# Main_Board_V1_0.net
KiCad netlist of a schematic drawn in EAGLE
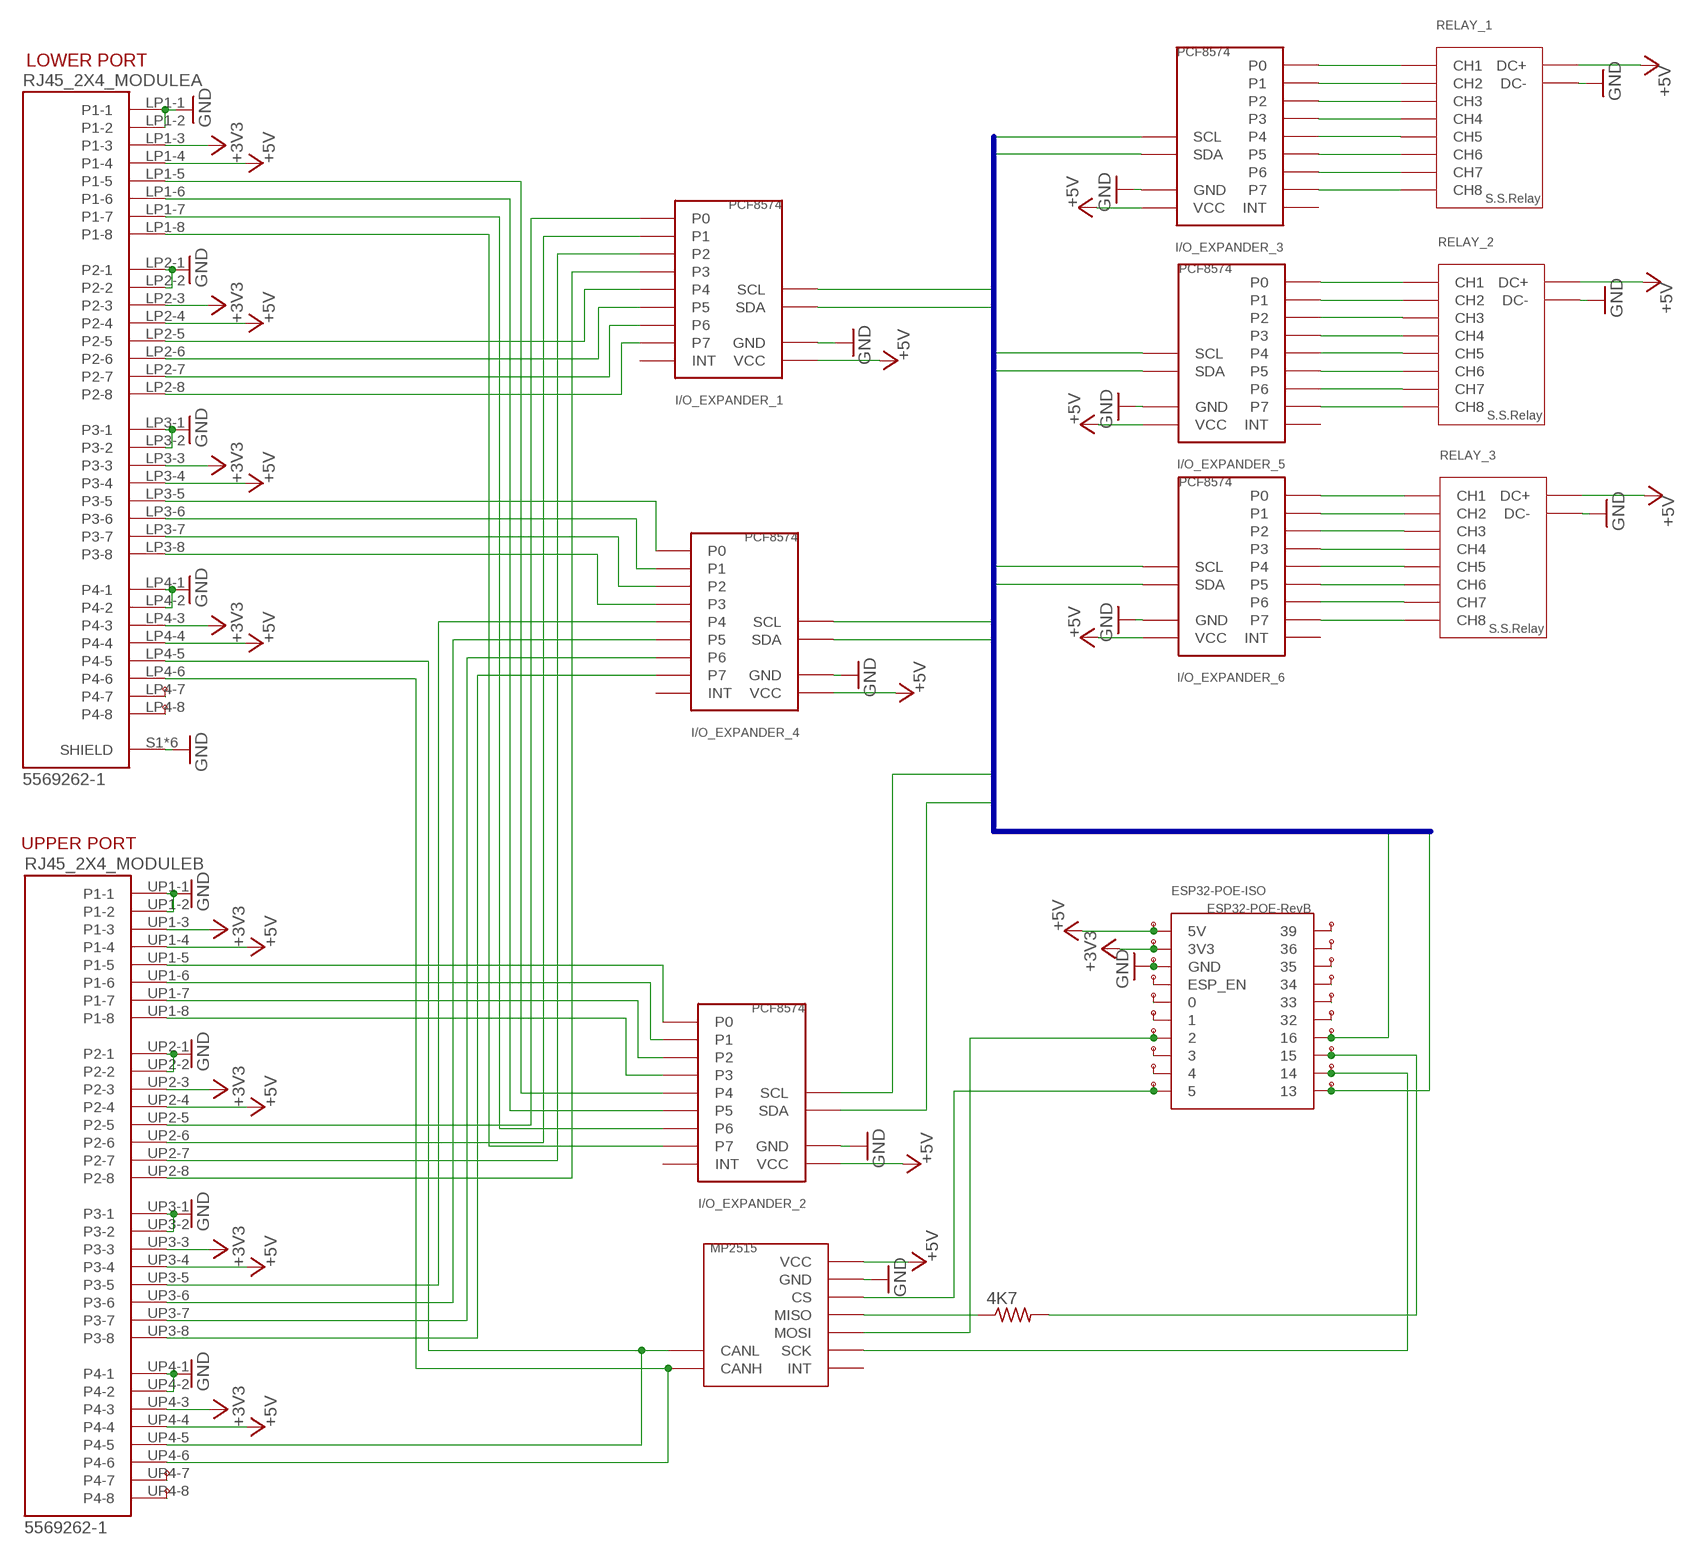
[diagram p0: schematic, sheet 1]

(export (version "E")
  (design (tool "Eeschema 10.0.6"))
  (components
    (comp (ref "4K7")
      (value "R-US_0207/10")
      (footprint "eagle-import:0207_10")
      (libsource (lib "eagle-import") (part "R-US_0207/10"))
    )
    (comp (ref "ESP32-POE-ISO")
      (value "ESP-POE")
      (footprint "eagle-import:ESP-POE")
      (libsource (lib "eagle-import") (part "ESP-POE"))
    )
    (comp (ref "I/O_EXPANDER_1")
      (value "PCF8574-MODULE_ESPELHADO")
      (footprint "eagle-import:PCF8574-MODULE_ESPELHADO")
      (libsource (lib "eagle-import") (part "PCF8574-MODULE_ESPELHADO"))
    )
    (comp (ref "I/O_EXPANDER_2")
      (value "PCF8574-MODULE_ESPELHADO")
      (footprint "eagle-import:PCF8574-MODULE_ESPELHADO")
      (libsource (lib "eagle-import") (part "PCF8574-MODULE_ESPELHADO"))
    )
    (comp (ref "I/O_EXPANDER_3")
      (value "PCF8574-MODULE_ESPELHADO")
      (footprint "eagle-import:PCF8574-MODULE_ESPELHADO")
      (libsource (lib "eagle-import") (part "PCF8574-MODULE_ESPELHADO"))
    )
    (comp (ref "I/O_EXPANDER_4")
      (value "PCF8574-MODULE_ESPELHADO")
      (footprint "eagle-import:PCF8574-MODULE_ESPELHADO")
      (libsource (lib "eagle-import") (part "PCF8574-MODULE_ESPELHADO"))
    )
    (comp (ref "I/O_EXPANDER_5")
      (value "PCF8574-MODULE_ESPELHADO")
      (footprint "eagle-import:PCF8574-MODULE_ESPELHADO")
      (libsource (lib "eagle-import") (part "PCF8574-MODULE_ESPELHADO"))
    )
    (comp (ref "I/O_EXPANDER_6")
      (value "PCF8574-MODULE_ESPELHADO")
      (footprint "eagle-import:PCF8574-MODULE_ESPELHADO")
      (libsource (lib "eagle-import") (part "PCF8574-MODULE_ESPELHADO"))
    )
    (comp (ref "RELAY_1")
      (value "SSR_M_FULL_SEM_LIGACOES")
      (footprint "eagle-import:SSR_M_SEM_LIGACOES")
      (libsource (lib "eagle-import") (part "SSR_M_FULL_SEM_LIGACOES"))
    )
    (comp (ref "RELAY_2")
      (value "SSR_M_FULL_SEM_LIGACOES")
      (footprint "eagle-import:SSR_M_SEM_LIGACOES")
      (libsource (lib "eagle-import") (part "SSR_M_FULL_SEM_LIGACOES"))
    )
    (comp (ref "RELAY_3")
      (value "SSR_M_FULL_SEM_LIGACOES")
      (footprint "eagle-import:SSR_M_SEM_LIGACOES")
      (libsource (lib "eagle-import") (part "SSR_M_FULL_SEM_LIGACOES"))
    )
    (comp (ref "RJ45_2X4_MODULE")
      (value "5569262-1")
      (footprint "eagle-import:TE_5569262-1")
      (fields (field (name "MF") "TE Connectivity"))
      (libsource (lib "eagle-import") (part "5569262-1"))
    )
    (comp (ref "U$1") (value "TP") (footprint "eagle-import:TP") (libsource (lib "eagle-import") (part "TP")))
    (comp (ref "U$2") (value "TP") (footprint "eagle-import:TP") (libsource (lib "eagle-import") (part "TP")))
    (comp (ref "U$4") (value "TP") (footprint "eagle-import:TP") (libsource (lib "eagle-import") (part "TP")))
    (comp (ref "U$5") (value "TP") (footprint "eagle-import:TP") (libsource (lib "eagle-import") (part "TP")))
    (comp (ref "U$6") (value "TP") (footprint "eagle-import:TP") (libsource (lib "eagle-import") (part "TP")))
    (comp (ref "U$7") (value "TP") (footprint "eagle-import:TP") (libsource (lib "eagle-import") (part "TP")))
    (comp (ref "U$8") (value "TP") (footprint "eagle-import:TP") (libsource (lib "eagle-import") (part "TP")))
    (comp (ref "U$9") (value "TP") (footprint "eagle-import:TP") (libsource (lib "eagle-import") (part "TP")))
    (comp (ref "U$10")
      (value "TP")
      (footprint "eagle-import:TP")
      (libsource (lib "eagle-import") (part "TP"))
    )
    (comp (ref "U$11")
      (value "TP")
      (footprint "eagle-import:TP")
      (libsource (lib "eagle-import") (part "TP"))
    )
    (comp (ref "U$12")
      (value "TP")
      (footprint "eagle-import:TP")
      (libsource (lib "eagle-import") (part "TP"))
    )
    (comp (ref "U$13")
      (value "TP")
      (footprint "eagle-import:TP")
      (libsource (lib "eagle-import") (part "TP"))
    )
    (comp (ref "U$14")
      (value "TP")
      (footprint "eagle-import:TP")
      (libsource (lib "eagle-import") (part "TP"))
    )
    (comp (ref "U$15")
      (value "TP")
      (footprint "eagle-import:TP")
      (libsource (lib "eagle-import") (part "TP"))
    )
    (comp (ref "U$16")
      (value "TP")
      (footprint "eagle-import:TP")
      (libsource (lib "eagle-import") (part "TP"))
    )
    (comp (ref "U$17")
      (value "TP")
      (footprint "eagle-import:TP")
      (libsource (lib "eagle-import") (part "TP"))
    )
    (comp (ref "U$18")
      (value "TP")
      (footprint "eagle-import:TP")
      (libsource (lib "eagle-import") (part "TP"))
    )
    (comp (ref "U$19")
      (value "TP")
      (footprint "eagle-import:TP")
      (libsource (lib "eagle-import") (part "TP"))
    )
    (comp (ref "U$20")
      (value "TP")
      (footprint "eagle-import:TP")
      (libsource (lib "eagle-import") (part "TP"))
    )
    (comp (ref "U$21")
      (value "TP")
      (footprint "eagle-import:TP")
      (libsource (lib "eagle-import") (part "TP"))
    )
    (comp (ref "U$22")
      (value "TP")
      (footprint "eagle-import:TP")
      (libsource (lib "eagle-import") (part "TP"))
    )
    (comp (ref "U$23")
      (value "TP")
      (footprint "eagle-import:TP")
      (libsource (lib "eagle-import") (part "TP"))
    )
    (comp (ref "U$24")
      (value "TP")
      (footprint "eagle-import:TP")
      (libsource (lib "eagle-import") (part "TP"))
    )
    (comp (ref "U$25")
      (value "TP")
      (footprint "eagle-import:TP")
      (libsource (lib "eagle-import") (part "TP"))
    )
    (comp (ref "U$26")
      (value "MCP2515_MODULE_SEM_LIGACOES")
      (footprint "eagle-import:MCP2515_MODULE_SEM_LIGACOES")
      (libsource (lib "eagle-import") (part "MCP2515_MODULE_SEM_LIGACOES"))
    )
  )
  (nets
    (net (code "1") (name "+3V3") (class "Default")
      (node (ref "ESP32-POE-ISO") (pin "3V3") (pinfunction "3V3_3V3") (pintype "bidirectional"))
      (node (ref "RJ45_2X4_MODULE") (pin "LP1-3") (pinfunction "P1-3_LP1-3") (pintype "passive"))
      (node (ref "RJ45_2X4_MODULE") (pin "LP2-3") (pinfunction "P2-3_LP2-3") (pintype "passive"))
      (node (ref "RJ45_2X4_MODULE") (pin "LP3-3") (pinfunction "P3-3_LP3-3") (pintype "passive"))
      (node (ref "RJ45_2X4_MODULE") (pin "LP4-3") (pinfunction "P4-3_LP4-3") (pintype "passive"))
      (node (ref "RJ45_2X4_MODULE") (pin "UP1-3") (pinfunction "P1-3_UP1-3") (pintype "passive"))
      (node (ref "RJ45_2X4_MODULE") (pin "UP2-3") (pinfunction "P2-3_UP2-3") (pintype "passive"))
      (node (ref "RJ45_2X4_MODULE") (pin "UP3-3") (pinfunction "P3-3_UP3-3") (pintype "passive"))
      (node (ref "RJ45_2X4_MODULE") (pin "UP4-3") (pinfunction "P4-3_UP4-3") (pintype "passive"))
      (node (ref "U$6") (pin "P$1") (pinfunction "P$1_P$1") (pintype "bidirectional"))
    )
    (net (code "2") (name "+5V") (class "Default")
      (node (ref "ESP32-POE-ISO") (pin "5V") (pinfunction "5V_5V") (pintype "bidirectional"))
      (node (ref "I/O_EXPANDER_1") (pin "VCC") (pinfunction "VCC_VCC") (pintype "bidirectional"))
      (node (ref "I/O_EXPANDER_2") (pin "VCC") (pinfunction "VCC_VCC") (pintype "bidirectional"))
      (node (ref "I/O_EXPANDER_3") (pin "VCC") (pinfunction "VCC_VCC") (pintype "bidirectional"))
      (node (ref "I/O_EXPANDER_4") (pin "VCC") (pinfunction "VCC_VCC") (pintype "bidirectional"))
      (node (ref "I/O_EXPANDER_5") (pin "VCC") (pinfunction "VCC_VCC") (pintype "bidirectional"))
      (node (ref "I/O_EXPANDER_6") (pin "VCC") (pinfunction "VCC_VCC") (pintype "bidirectional"))
      (node (ref "RELAY_1") (pin "DC+") (pinfunction "DC+_DC+") (pintype "bidirectional"))
      (node (ref "RELAY_2") (pin "DC+") (pinfunction "DC+_DC+") (pintype "bidirectional"))
      (node (ref "RELAY_3") (pin "DC+") (pinfunction "DC+_DC+") (pintype "bidirectional"))
      (node (ref "RJ45_2X4_MODULE") (pin "LP1-4") (pinfunction "P1-4_LP1-4") (pintype "passive"))
      (node (ref "RJ45_2X4_MODULE") (pin "LP2-4") (pinfunction "P2-4_LP2-4") (pintype "passive"))
      (node (ref "RJ45_2X4_MODULE") (pin "LP3-4") (pinfunction "P3-4_LP3-4") (pintype "passive"))
      (node (ref "RJ45_2X4_MODULE") (pin "LP4-4") (pinfunction "P4-4_LP4-4") (pintype "passive"))
      (node (ref "RJ45_2X4_MODULE") (pin "UP1-4") (pinfunction "P1-4_UP1-4") (pintype "passive"))
      (node (ref "RJ45_2X4_MODULE") (pin "UP2-4") (pinfunction "P2-4_UP2-4") (pintype "passive"))
      (node (ref "RJ45_2X4_MODULE") (pin "UP3-4") (pinfunction "P3-4_UP3-4") (pintype "passive"))
      (node (ref "RJ45_2X4_MODULE") (pin "UP4-4") (pinfunction "P4-4_UP4-4") (pintype "passive"))
      (node (ref "U$2") (pin "P$1") (pinfunction "P$1_P$1") (pintype "bidirectional"))
      (node (ref "U$26") (pin "VCC") (pinfunction "VCC_VCC") (pintype "bidirectional"))
    )
    (net (code "3") (name "/SCL") (class "Default")
      (node (ref "ESP32-POE-ISO") (pin "16") (pinfunction "16_16") (pintype "bidirectional"))
      (node (ref "I/O_EXPANDER_1") (pin "SCL") (pinfunction "SCL_SCL") (pintype "bidirectional"))
      (node (ref "I/O_EXPANDER_2") (pin "SCL") (pinfunction "SCL_SCL") (pintype "bidirectional"))
      (node (ref "I/O_EXPANDER_3") (pin "SCL") (pinfunction "SCL_SCL") (pintype "bidirectional"))
      (node (ref "I/O_EXPANDER_4") (pin "SCL") (pinfunction "SCL_SCL") (pintype "bidirectional"))
      (node (ref "I/O_EXPANDER_5") (pin "SCL") (pinfunction "SCL_SCL") (pintype "bidirectional"))
      (node (ref "I/O_EXPANDER_6") (pin "SCL") (pinfunction "SCL_SCL") (pintype "bidirectional"))
      (node (ref "U$21") (pin "P$1") (pinfunction "P$1_P$1") (pintype "bidirectional"))
    )
    (net (code "4") (name "/SDA") (class "Default")
      (node (ref "ESP32-POE-ISO") (pin "13") (pinfunction "13_13") (pintype "bidirectional"))
      (node (ref "I/O_EXPANDER_1") (pin "SDA") (pinfunction "SDA_SDA") (pintype "bidirectional"))
      (node (ref "I/O_EXPANDER_2") (pin "SDA") (pinfunction "SDA_SDA") (pintype "bidirectional"))
      (node (ref "I/O_EXPANDER_3") (pin "SDA") (pinfunction "SDA_SDA") (pintype "bidirectional"))
      (node (ref "I/O_EXPANDER_4") (pin "SDA") (pinfunction "SDA_SDA") (pintype "bidirectional"))
      (node (ref "I/O_EXPANDER_5") (pin "SDA") (pinfunction "SDA_SDA") (pintype "bidirectional"))
      (node (ref "I/O_EXPANDER_6") (pin "SDA") (pinfunction "SDA_SDA") (pintype "bidirectional"))
      (node (ref "U$24") (pin "P$1") (pinfunction "P$1_P$1") (pintype "bidirectional"))
    )
    (net (code "5") (name "GND") (class "Default")
      (node (ref "ESP32-POE-ISO") (pin "GND") (pinfunction "GND_GND") (pintype "bidirectional"))
      (node (ref "I/O_EXPANDER_1") (pin "GND") (pinfunction "GND_GND") (pintype "bidirectional"))
      (node (ref "I/O_EXPANDER_2") (pin "GND") (pinfunction "GND_GND") (pintype "bidirectional"))
      (node (ref "I/O_EXPANDER_3") (pin "GND") (pinfunction "GND_GND") (pintype "bidirectional"))
      (node (ref "I/O_EXPANDER_4") (pin "GND") (pinfunction "GND_GND") (pintype "bidirectional"))
      (node (ref "I/O_EXPANDER_5") (pin "GND") (pinfunction "GND_GND") (pintype "bidirectional"))
      (node (ref "I/O_EXPANDER_6") (pin "GND") (pinfunction "GND_GND") (pintype "bidirectional"))
      (node (ref "RELAY_1") (pin "DC-") (pinfunction "DC-_DC-") (pintype "bidirectional"))
      (node (ref "RELAY_2") (pin "DC-") (pinfunction "DC-_DC-") (pintype "bidirectional"))
      (node (ref "RELAY_3") (pin "DC-") (pinfunction "DC-_DC-") (pintype "bidirectional"))
      (node (ref "RJ45_2X4_MODULE") (pin "LP1-1") (pinfunction "P1-1_LP1-1") (pintype "passive"))
      (node (ref "RJ45_2X4_MODULE") (pin "LP1-2") (pinfunction "P1-2_LP1-2") (pintype "passive"))
      (node (ref "RJ45_2X4_MODULE") (pin "LP2-1") (pinfunction "P2-1_LP2-1") (pintype "passive"))
      (node (ref "RJ45_2X4_MODULE") (pin "LP2-2") (pinfunction "P2-2_LP2-2") (pintype "passive"))
      (node (ref "RJ45_2X4_MODULE") (pin "LP3-1") (pinfunction "P3-1_LP3-1") (pintype "passive"))
      (node (ref "RJ45_2X4_MODULE") (pin "LP3-2") (pinfunction "P3-2_LP3-2") (pintype "passive"))
      (node (ref "RJ45_2X4_MODULE") (pin "LP4-1") (pinfunction "P4-1_LP4-1") (pintype "passive"))
      (node (ref "RJ45_2X4_MODULE") (pin "LP4-2") (pinfunction "P4-2_LP4-2") (pintype "passive"))
      (node (ref "RJ45_2X4_MODULE") (pin "S1") (pinfunction "SHIELD_S1") (pintype "passive"))
      (node (ref "RJ45_2X4_MODULE") (pin "S2") (pinfunction "SHIELD_S2") (pintype "passive"))
      (node (ref "RJ45_2X4_MODULE") (pin "S3") (pinfunction "SHIELD_S3") (pintype "passive"))
      (node (ref "RJ45_2X4_MODULE") (pin "S4") (pinfunction "SHIELD_S4") (pintype "passive"))
      (node (ref "RJ45_2X4_MODULE") (pin "S5") (pinfunction "SHIELD_S5") (pintype "passive"))
      (node (ref "RJ45_2X4_MODULE") (pin "S6") (pinfunction "SHIELD_S6") (pintype "passive"))
      (node (ref "RJ45_2X4_MODULE") (pin "UP1-1") (pinfunction "P1-1_UP1-1") (pintype "passive"))
      (node (ref "RJ45_2X4_MODULE") (pin "UP1-2") (pinfunction "P1-2_UP1-2") (pintype "passive"))
      (node (ref "RJ45_2X4_MODULE") (pin "UP2-1") (pinfunction "P2-1_UP2-1") (pintype "passive"))
      (node (ref "RJ45_2X4_MODULE") (pin "UP2-2") (pinfunction "P2-2_UP2-2") (pintype "passive"))
      (node (ref "RJ45_2X4_MODULE") (pin "UP3-1") (pinfunction "P3-1_UP3-1") (pintype "passive"))
      (node (ref "RJ45_2X4_MODULE") (pin "UP3-2") (pinfunction "P3-2_UP3-2") (pintype "passive"))
      (node (ref "RJ45_2X4_MODULE") (pin "UP4-1") (pinfunction "P4-1_UP4-1") (pintype "passive"))
      (node (ref "RJ45_2X4_MODULE") (pin "UP4-2") (pinfunction "P4-2_UP4-2") (pintype "passive"))
      (node (ref "U$26") (pin "GND") (pinfunction "GND_GND") (pintype "bidirectional"))
      (node (ref "U$7") (pin "P$1") (pinfunction "P$1_P$1") (pintype "bidirectional"))
    )
    (net (code "6") (name "Net-(4K7-Pad1)") (class "Default")
      (node (ref "4K7") (pin "1") (pinfunction "1_1") (pintype "passive"))
      (node (ref "U$26") (pin "MISO") (pinfunction "MISO_MISO") (pintype "bidirectional"))
    )
    (net (code "7") (name "Net-(4K7-Pad2)") (class "Default")
      (node (ref "4K7") (pin "2") (pinfunction "2_2") (pintype "passive"))
      (node (ref "ESP32-POE-ISO") (pin "15") (pinfunction "15_15") (pintype "bidirectional"))
      (node (ref "U$22") (pin "P$1") (pinfunction "P$1_P$1") (pintype "bidirectional"))
    )
    (net (code "8") (name "Net-(ESP32-POE-ISO-Pad0)") (class "Default")
      (node (ref "ESP32-POE-ISO") (pin "0") (pinfunction "0_0") (pintype "bidirectional"))
      (node (ref "U$9") (pin "P$1") (pinfunction "P$1_P$1") (pintype "bidirectional"))
    )
    (net (code "9") (name "Net-(ESP32-POE-ISO-Pad1)") (class "Default")
      (node (ref "ESP32-POE-ISO") (pin "1") (pinfunction "1_1") (pintype "bidirectional"))
      (node (ref "U$10") (pin "P$1") (pinfunction "P$1_P$1") (pintype "bidirectional"))
    )
    (net (code "10") (name "Net-(ESP32-POE-ISO-Pad2)") (class "Default")
      (node (ref "ESP32-POE-ISO") (pin "2") (pinfunction "2_2") (pintype "bidirectional"))
      (node (ref "U$11") (pin "P$1") (pinfunction "P$1_P$1") (pintype "bidirectional"))
      (node (ref "U$26") (pin "MOSI") (pinfunction "MOSI_MOSI") (pintype "bidirectional"))
    )
    (net (code "11") (name "Net-(ESP32-POE-ISO-Pad3)") (class "Default")
      (node (ref "ESP32-POE-ISO") (pin "3") (pinfunction "3_3") (pintype "bidirectional"))
      (node (ref "U$12") (pin "P$1") (pinfunction "P$1_P$1") (pintype "bidirectional"))
    )
    (net (code "12") (name "Net-(ESP32-POE-ISO-Pad4)") (class "Default")
      (node (ref "ESP32-POE-ISO") (pin "4") (pinfunction "4_4") (pintype "bidirectional"))
      (node (ref "U$13") (pin "P$1") (pinfunction "P$1_P$1") (pintype "bidirectional"))
    )
    (net (code "13") (name "Net-(ESP32-POE-ISO-Pad5)") (class "Default")
      (node (ref "ESP32-POE-ISO") (pin "5") (pinfunction "5_5") (pintype "bidirectional"))
      (node (ref "U$14") (pin "P$1") (pinfunction "P$1_P$1") (pintype "bidirectional"))
      (node (ref "U$26") (pin "CS") (pinfunction "CS_CS") (pintype "bidirectional"))
    )
    (net (code "14") (name "Net-(ESP32-POE-ISO-Pad14)") (class "Default")
      (node (ref "ESP32-POE-ISO") (pin "14") (pinfunction "14_14") (pintype "bidirectional"))
      (node (ref "U$23") (pin "P$1") (pinfunction "P$1_P$1") (pintype "bidirectional"))
      (node (ref "U$26") (pin "SCK") (pinfunction "SCK_SCK") (pintype "bidirectional"))
    )
    (net (code "15") (name "Net-(ESP32-POE-ISO-Pad32)") (class "Default")
      (node (ref "ESP32-POE-ISO") (pin "32") (pinfunction "32_32") (pintype "bidirectional"))
      (node (ref "U$20") (pin "P$1") (pinfunction "P$1_P$1") (pintype "bidirectional"))
    )
    (net (code "16") (name "Net-(ESP32-POE-ISO-Pad33)") (class "Default")
      (node (ref "ESP32-POE-ISO") (pin "33") (pinfunction "33_33") (pintype "bidirectional"))
      (node (ref "U$19") (pin "P$1") (pinfunction "P$1_P$1") (pintype "bidirectional"))
    )
    (net (code "17") (name "Net-(ESP32-POE-ISO-Pad34)") (class "Default")
      (node (ref "ESP32-POE-ISO") (pin "34") (pinfunction "34_34") (pintype "bidirectional"))
      (node (ref "U$18") (pin "P$1") (pinfunction "P$1_P$1") (pintype "bidirectional"))
    )
    (net (code "18") (name "Net-(ESP32-POE-ISO-Pad35)") (class "Default")
      (node (ref "ESP32-POE-ISO") (pin "35") (pinfunction "35_35") (pintype "bidirectional"))
      (node (ref "U$17") (pin "P$1") (pinfunction "P$1_P$1") (pintype "bidirectional"))
    )
    (net (code "19") (name "Net-(ESP32-POE-ISO-Pad36)") (class "Default")
      (node (ref "ESP32-POE-ISO") (pin "36") (pinfunction "36_36") (pintype "bidirectional"))
      (node (ref "U$16") (pin "P$1") (pinfunction "P$1_P$1") (pintype "bidirectional"))
    )
    (net (code "20") (name "Net-(ESP32-POE-ISO-Pad39)") (class "Default")
      (node (ref "ESP32-POE-ISO") (pin "39") (pinfunction "39_39") (pintype "bidirectional"))
      (node (ref "U$15") (pin "P$1") (pinfunction "P$1_P$1") (pintype "bidirectional"))
    )
    (net (code "21") (name "Net-(ESP32-POE-ISO-PadESP_EN)") (class "Default")
      (node (ref "ESP32-POE-ISO") (pin "ESP_EN") (pinfunction "ESP_EN_ESP_EN") (pintype "bidirectional"))
      (node (ref "U$8") (pin "P$1") (pinfunction "P$1_P$1") (pintype "bidirectional"))
    )
    (net (code "22") (name "Net-(I/O_EXPANDER_3-PadP0)") (class "Default")
      (node (ref "I/O_EXPANDER_3") (pin "P0") (pinfunction "P0_P0") (pintype "bidirectional"))
      (node (ref "RELAY_1") (pin "CH1") (pinfunction "CH1_CH1") (pintype "bidirectional"))
    )
    (net (code "23") (name "Net-(I/O_EXPANDER_3-PadP1)") (class "Default")
      (node (ref "I/O_EXPANDER_3") (pin "P1") (pinfunction "P1_P1") (pintype "bidirectional"))
      (node (ref "RELAY_1") (pin "CH2") (pinfunction "CH2_CH2") (pintype "bidirectional"))
    )
    (net (code "24") (name "Net-(I/O_EXPANDER_3-PadP2)") (class "Default")
      (node (ref "I/O_EXPANDER_3") (pin "P2") (pinfunction "P2_P2") (pintype "bidirectional"))
      (node (ref "RELAY_1") (pin "CH3") (pinfunction "CH3_CH3") (pintype "bidirectional"))
    )
    (net (code "25") (name "Net-(I/O_EXPANDER_3-PadP3)") (class "Default")
      (node (ref "I/O_EXPANDER_3") (pin "P3") (pinfunction "P3_P3") (pintype "bidirectional"))
      (node (ref "RELAY_1") (pin "CH4") (pinfunction "CH4_CH4") (pintype "bidirectional"))
    )
    (net (code "26") (name "Net-(I/O_EXPANDER_3-PadP4)") (class "Default")
      (node (ref "I/O_EXPANDER_3") (pin "P4") (pinfunction "P4_P4") (pintype "bidirectional"))
      (node (ref "RELAY_1") (pin "CH5") (pinfunction "CH5_CH5") (pintype "bidirectional"))
    )
    (net (code "27") (name "Net-(I/O_EXPANDER_3-PadP5)") (class "Default")
      (node (ref "I/O_EXPANDER_3") (pin "P5") (pinfunction "P5_P5") (pintype "bidirectional"))
      (node (ref "RELAY_1") (pin "CH6") (pinfunction "CH6_CH6") (pintype "bidirectional"))
    )
    (net (code "28") (name "Net-(I/O_EXPANDER_3-PadP6)") (class "Default")
      (node (ref "I/O_EXPANDER_3") (pin "P6") (pinfunction "P6_P6") (pintype "bidirectional"))
      (node (ref "RELAY_1") (pin "CH7") (pinfunction "CH7_CH7") (pintype "bidirectional"))
    )
    (net (code "29") (name "Net-(I/O_EXPANDER_3-PadP7)") (class "Default")
      (node (ref "I/O_EXPANDER_3") (pin "P7") (pinfunction "P7_P7") (pintype "bidirectional"))
      (node (ref "RELAY_1") (pin "CH8") (pinfunction "CH8_CH8") (pintype "bidirectional"))
    )
    (net (code "30") (name "Net-(I/O_EXPANDER_5-PadP0)") (class "Default")
      (node (ref "I/O_EXPANDER_5") (pin "P0") (pinfunction "P0_P0") (pintype "bidirectional"))
      (node (ref "RELAY_2") (pin "CH1") (pinfunction "CH1_CH1") (pintype "bidirectional"))
    )
    (net (code "31") (name "Net-(I/O_EXPANDER_5-PadP1)") (class "Default")
      (node (ref "I/O_EXPANDER_5") (pin "P1") (pinfunction "P1_P1") (pintype "bidirectional"))
      (node (ref "RELAY_2") (pin "CH2") (pinfunction "CH2_CH2") (pintype "bidirectional"))
    )
    (net (code "32") (name "Net-(I/O_EXPANDER_5-PadP2)") (class "Default")
      (node (ref "I/O_EXPANDER_5") (pin "P2") (pinfunction "P2_P2") (pintype "bidirectional"))
      (node (ref "RELAY_2") (pin "CH3") (pinfunction "CH3_CH3") (pintype "bidirectional"))
    )
    (net (code "33") (name "Net-(I/O_EXPANDER_5-PadP3)") (class "Default")
      (node (ref "I/O_EXPANDER_5") (pin "P3") (pinfunction "P3_P3") (pintype "bidirectional"))
      (node (ref "RELAY_2") (pin "CH4") (pinfunction "CH4_CH4") (pintype "bidirectional"))
    )
    (net (code "34") (name "Net-(I/O_EXPANDER_5-PadP4)") (class "Default")
      (node (ref "I/O_EXPANDER_5") (pin "P4") (pinfunction "P4_P4") (pintype "bidirectional"))
      (node (ref "RELAY_2") (pin "CH5") (pinfunction "CH5_CH5") (pintype "bidirectional"))
    )
    (net (code "35") (name "Net-(I/O_EXPANDER_5-PadP5)") (class "Default")
      (node (ref "I/O_EXPANDER_5") (pin "P5") (pinfunction "P5_P5") (pintype "bidirectional"))
      (node (ref "RELAY_2") (pin "CH6") (pinfunction "CH6_CH6") (pintype "bidirectional"))
    )
    (net (code "36") (name "Net-(I/O_EXPANDER_5-PadP6)") (class "Default")
      (node (ref "I/O_EXPANDER_5") (pin "P6") (pinfunction "P6_P6") (pintype "bidirectional"))
      (node (ref "RELAY_2") (pin "CH7") (pinfunction "CH7_CH7") (pintype "bidirectional"))
    )
    (net (code "37") (name "Net-(I/O_EXPANDER_5-PadP7)") (class "Default")
      (node (ref "I/O_EXPANDER_5") (pin "P7") (pinfunction "P7_P7") (pintype "bidirectional"))
      (node (ref "RELAY_2") (pin "CH8") (pinfunction "CH8_CH8") (pintype "bidirectional"))
    )
    (net (code "38") (name "Net-(I/O_EXPANDER_6-PadP0)") (class "Default")
      (node (ref "I/O_EXPANDER_6") (pin "P0") (pinfunction "P0_P0") (pintype "bidirectional"))
      (node (ref "RELAY_3") (pin "CH1") (pinfunction "CH1_CH1") (pintype "bidirectional"))
    )
    (net (code "39") (name "Net-(I/O_EXPANDER_6-PadP1)") (class "Default")
      (node (ref "I/O_EXPANDER_6") (pin "P1") (pinfunction "P1_P1") (pintype "bidirectional"))
      (node (ref "RELAY_3") (pin "CH2") (pinfunction "CH2_CH2") (pintype "bidirectional"))
    )
    (net (code "40") (name "Net-(I/O_EXPANDER_6-PadP2)") (class "Default")
      (node (ref "I/O_EXPANDER_6") (pin "P2") (pinfunction "P2_P2") (pintype "bidirectional"))
      (node (ref "RELAY_3") (pin "CH3") (pinfunction "CH3_CH3") (pintype "bidirectional"))
    )
    (net (code "41") (name "Net-(I/O_EXPANDER_6-PadP3)") (class "Default")
      (node (ref "I/O_EXPANDER_6") (pin "P3") (pinfunction "P3_P3") (pintype "bidirectional"))
      (node (ref "RELAY_3") (pin "CH4") (pinfunction "CH4_CH4") (pintype "bidirectional"))
    )
    (net (code "42") (name "Net-(I/O_EXPANDER_6-PadP4)") (class "Default")
      (node (ref "I/O_EXPANDER_6") (pin "P4") (pinfunction "P4_P4") (pintype "bidirectional"))
      (node (ref "RELAY_3") (pin "CH5") (pinfunction "CH5_CH5") (pintype "bidirectional"))
    )
    (net (code "43") (name "Net-(I/O_EXPANDER_6-PadP5)") (class "Default")
      (node (ref "I/O_EXPANDER_6") (pin "P5") (pinfunction "P5_P5") (pintype "bidirectional"))
      (node (ref "RELAY_3") (pin "CH6") (pinfunction "CH6_CH6") (pintype "bidirectional"))
    )
    (net (code "44") (name "Net-(I/O_EXPANDER_6-PadP6)") (class "Default")
      (node (ref "I/O_EXPANDER_6") (pin "P6") (pinfunction "P6_P6") (pintype "bidirectional"))
      (node (ref "RELAY_3") (pin "CH7") (pinfunction "CH7_CH7") (pintype "bidirectional"))
    )
    (net (code "45") (name "Net-(I/O_EXPANDER_6-PadP7)") (class "Default")
      (node (ref "I/O_EXPANDER_6") (pin "P7") (pinfunction "P7_P7") (pintype "bidirectional"))
      (node (ref "RELAY_3") (pin "CH8") (pinfunction "CH8_CH8") (pintype "bidirectional"))
    )
    (net (code "46") (name "Net-(RJ45_2X4_MODULEA-P1-5)") (class "Default")
      (node (ref "I/O_EXPANDER_2") (pin "P4") (pinfunction "P4_P4") (pintype "bidirectional"))
      (node (ref "RJ45_2X4_MODULE") (pin "LP1-5") (pinfunction "P1-5_LP1-5") (pintype "passive"))
    )
    (net (code "47") (name "Net-(RJ45_2X4_MODULEA-P1-6)") (class "Default")
      (node (ref "I/O_EXPANDER_2") (pin "P5") (pinfunction "P5_P5") (pintype "bidirectional"))
      (node (ref "RJ45_2X4_MODULE") (pin "LP1-6") (pinfunction "P1-6_LP1-6") (pintype "passive"))
    )
    (net (code "48") (name "Net-(RJ45_2X4_MODULEA-P1-7)") (class "Default")
      (node (ref "I/O_EXPANDER_2") (pin "P6") (pinfunction "P6_P6") (pintype "bidirectional"))
      (node (ref "RJ45_2X4_MODULE") (pin "LP1-7") (pinfunction "P1-7_LP1-7") (pintype "passive"))
    )
    (net (code "49") (name "Net-(RJ45_2X4_MODULEA-P1-8)") (class "Default")
      (node (ref "I/O_EXPANDER_2") (pin "P7") (pinfunction "P7_P7") (pintype "bidirectional"))
      (node (ref "RJ45_2X4_MODULE") (pin "LP1-8") (pinfunction "P1-8_LP1-8") (pintype "passive"))
    )
    (net (code "50") (name "Net-(RJ45_2X4_MODULEA-P2-5)") (class "Default")
      (node (ref "I/O_EXPANDER_1") (pin "P4") (pinfunction "P4_P4") (pintype "bidirectional"))
      (node (ref "RJ45_2X4_MODULE") (pin "LP2-5") (pinfunction "P2-5_LP2-5") (pintype "passive"))
    )
    (net (code "51") (name "Net-(RJ45_2X4_MODULEA-P2-6)") (class "Default")
      (node (ref "I/O_EXPANDER_1") (pin "P5") (pinfunction "P5_P5") (pintype "bidirectional"))
      (node (ref "RJ45_2X4_MODULE") (pin "LP2-6") (pinfunction "P2-6_LP2-6") (pintype "passive"))
    )
    (net (code "52") (name "Net-(RJ45_2X4_MODULEA-P2-7)") (class "Default")
      (node (ref "I/O_EXPANDER_1") (pin "P6") (pinfunction "P6_P6") (pintype "bidirectional"))
      (node (ref "RJ45_2X4_MODULE") (pin "LP2-7") (pinfunction "P2-7_LP2-7") (pintype "passive"))
    )
    (net (code "53") (name "Net-(RJ45_2X4_MODULEA-P2-8)") (class "Default")
      (node (ref "I/O_EXPANDER_1") (pin "P7") (pinfunction "P7_P7") (pintype "bidirectional"))
      (node (ref "RJ45_2X4_MODULE") (pin "LP2-8") (pinfunction "P2-8_LP2-8") (pintype "passive"))
    )
    (net (code "54") (name "Net-(RJ45_2X4_MODULEA-P3-5)") (class "Default")
      (node (ref "I/O_EXPANDER_4") (pin "P0") (pinfunction "P0_P0") (pintype "bidirectional"))
      (node (ref "RJ45_2X4_MODULE") (pin "LP3-5") (pinfunction "P3-5_LP3-5") (pintype "passive"))
    )
    (net (code "55") (name "Net-(RJ45_2X4_MODULEA-P3-6)") (class "Default")
      (node (ref "I/O_EXPANDER_4") (pin "P1") (pinfunction "P1_P1") (pintype "bidirectional"))
      (node (ref "RJ45_2X4_MODULE") (pin "LP3-6") (pinfunction "P3-6_LP3-6") (pintype "passive"))
    )
    (net (code "56") (name "Net-(RJ45_2X4_MODULEA-P3-7)") (class "Default")
      (node (ref "I/O_EXPANDER_4") (pin "P2") (pinfunction "P2_P2") (pintype "bidirectional"))
      (node (ref "RJ45_2X4_MODULE") (pin "LP3-7") (pinfunction "P3-7_LP3-7") (pintype "passive"))
    )
    (net (code "57") (name "Net-(RJ45_2X4_MODULEA-P3-8)") (class "Default")
      (node (ref "I/O_EXPANDER_4") (pin "P3") (pinfunction "P3_P3") (pintype "bidirectional"))
      (node (ref "RJ45_2X4_MODULE") (pin "LP3-8") (pinfunction "P3-8_LP3-8") (pintype "passive"))
    )
    (net (code "58") (name "Net-(RJ45_2X4_MODULEA-P4-5)") (class "Default")
      (node (ref "RJ45_2X4_MODULE") (pin "LP4-5") (pinfunction "P4-5_LP4-5") (pintype "passive"))
      (node (ref "RJ45_2X4_MODULE") (pin "UP4-5") (pinfunction "P4-5_UP4-5") (pintype "passive"))
      (node (ref "U$26") (pin "CL") (pinfunction "CANL_CL") (pintype "bidirectional"))
    )
    (net (code "59") (name "Net-(RJ45_2X4_MODULEA-P4-6)") (class "Default")
      (node (ref "RJ45_2X4_MODULE") (pin "LP4-6") (pinfunction "P4-6_LP4-6") (pintype "passive"))
      (node (ref "RJ45_2X4_MODULE") (pin "UP4-6") (pinfunction "P4-6_UP4-6") (pintype "passive"))
      (node (ref "U$26") (pin "CH") (pinfunction "CANH_CH") (pintype "bidirectional"))
    )
    (net (code "60") (name "Net-(RJ45_2X4_MODULEA-P4-7)") (class "Default")
      (node (ref "RJ45_2X4_MODULE") (pin "LP4-7") (pinfunction "P4-7_LP4-7") (pintype "passive"))
      (node (ref "U$5") (pin "P$1") (pinfunction "P$1_P$1") (pintype "bidirectional"))
    )
    (net (code "61") (name "Net-(RJ45_2X4_MODULEA-P4-8)") (class "Default")
      (node (ref "RJ45_2X4_MODULE") (pin "LP4-8") (pinfunction "P4-8_LP4-8") (pintype "passive"))
      (node (ref "U$25") (pin "P$1") (pinfunction "P$1_P$1") (pintype "bidirectional"))
    )
    (net (code "62") (name "Net-(RJ45_2X4_MODULEB-P1-5)") (class "Default")
      (node (ref "I/O_EXPANDER_2") (pin "P0") (pinfunction "P0_P0") (pintype "bidirectional"))
      (node (ref "RJ45_2X4_MODULE") (pin "UP1-5") (pinfunction "P1-5_UP1-5") (pintype "passive"))
    )
    (net (code "63") (name "Net-(RJ45_2X4_MODULEB-P1-6)") (class "Default")
      (node (ref "I/O_EXPANDER_2") (pin "P1") (pinfunction "P1_P1") (pintype "bidirectional"))
      (node (ref "RJ45_2X4_MODULE") (pin "UP1-6") (pinfunction "P1-6_UP1-6") (pintype "passive"))
    )
    (net (code "64") (name "Net-(RJ45_2X4_MODULEB-P1-7)") (class "Default")
      (node (ref "I/O_EXPANDER_2") (pin "P2") (pinfunction "P2_P2") (pintype "bidirectional"))
      (node (ref "RJ45_2X4_MODULE") (pin "UP1-7") (pinfunction "P1-7_UP1-7") (pintype "passive"))
    )
    (net (code "65") (name "Net-(RJ45_2X4_MODULEB-P1-8)") (class "Default")
      (node (ref "I/O_EXPANDER_2") (pin "P3") (pinfunction "P3_P3") (pintype "bidirectional"))
      (node (ref "RJ45_2X4_MODULE") (pin "UP1-8") (pinfunction "P1-8_UP1-8") (pintype "passive"))
    )
    (net (code "66") (name "Net-(RJ45_2X4_MODULEB-P2-5)") (class "Default")
      (node (ref "I/O_EXPANDER_1") (pin "P0") (pinfunction "P0_P0") (pintype "bidirectional"))
      (node (ref "RJ45_2X4_MODULE") (pin "UP2-5") (pinfunction "P2-5_UP2-5") (pintype "passive"))
    )
    (net (code "67") (name "Net-(RJ45_2X4_MODULEB-P2-6)") (class "Default")
      (node (ref "I/O_EXPANDER_1") (pin "P1") (pinfunction "P1_P1") (pintype "bidirectional"))
      (node (ref "RJ45_2X4_MODULE") (pin "UP2-6") (pinfunction "P2-6_UP2-6") (pintype "passive"))
    )
    (net (code "68") (name "Net-(RJ45_2X4_MODULEB-P2-7)") (class "Default")
      (node (ref "I/O_EXPANDER_1") (pin "P2") (pinfunction "P2_P2") (pintype "bidirectional"))
      (node (ref "RJ45_2X4_MODULE") (pin "UP2-7") (pinfunction "P2-7_UP2-7") (pintype "passive"))
    )
    (net (code "69") (name "Net-(RJ45_2X4_MODULEB-P2-8)") (class "Default")
      (node (ref "I/O_EXPANDER_1") (pin "P3") (pinfunction "P3_P3") (pintype "bidirectional"))
      (node (ref "RJ45_2X4_MODULE") (pin "UP2-8") (pinfunction "P2-8_UP2-8") (pintype "passive"))
    )
    (net (code "70") (name "Net-(RJ45_2X4_MODULEB-P3-5)") (class "Default")
      (node (ref "I/O_EXPANDER_4") (pin "P4") (pinfunction "P4_P4") (pintype "bidirectional"))
      (node (ref "RJ45_2X4_MODULE") (pin "UP3-5") (pinfunction "P3-5_UP3-5") (pintype "passive"))
    )
    (net (code "71") (name "Net-(RJ45_2X4_MODULEB-P3-6)") (class "Default")
      (node (ref "I/O_EXPANDER_4") (pin "P5") (pinfunction "P5_P5") (pintype "bidirectional"))
      (node (ref "RJ45_2X4_MODULE") (pin "UP3-6") (pinfunction "P3-6_UP3-6") (pintype "passive"))
    )
    (net (code "72") (name "Net-(RJ45_2X4_MODULEB-P3-7)") (class "Default")
      (node (ref "I/O_EXPANDER_4") (pin "P6") (pinfunction "P6_P6") (pintype "bidirectional"))
      (node (ref "RJ45_2X4_MODULE") (pin "UP3-7") (pinfunction "P3-7_UP3-7") (pintype "passive"))
    )
    (net (code "73") (name "Net-(RJ45_2X4_MODULEB-P3-8)") (class "Default")
      (node (ref "I/O_EXPANDER_4") (pin "P7") (pinfunction "P7_P7") (pintype "bidirectional"))
      (node (ref "RJ45_2X4_MODULE") (pin "UP3-8") (pinfunction "P3-8_UP3-8") (pintype "passive"))
    )
    (net (code "74") (name "Net-(RJ45_2X4_MODULEB-P4-7)") (class "Default")
      (node (ref "RJ45_2X4_MODULE") (pin "UP4-7") (pinfunction "P4-7_UP4-7") (pintype "passive"))
      (node (ref "U$1") (pin "P$1") (pinfunction "P$1_P$1") (pintype "bidirectional"))
    )
    (net (code "75") (name "Net-(RJ45_2X4_MODULEB-P4-8)") (class "Default")
      (node (ref "RJ45_2X4_MODULE") (pin "UP4-8") (pinfunction "P4-8_UP4-8") (pintype "passive"))
      (node (ref "U$4") (pin "P$1") (pinfunction "P$1_P$1") (pintype "bidirectional"))
    )
    (net (code "76") (name "unconnected-(I/O_EXPANDER_1-PadINT)") (class "Default")
      (node (ref "I/O_EXPANDER_1") (pin "INT") (pinfunction "INT_INT") (pintype "bidirectional"))
    )
    (net (code "77") (name "unconnected-(I/O_EXPANDER_2-PadINT)") (class "Default")
      (node (ref "I/O_EXPANDER_2") (pin "INT") (pinfunction "INT_INT") (pintype "bidirectional"))
    )
    (net (code "78") (name "unconnected-(I/O_EXPANDER_3-PadINT)") (class "Default")
      (node (ref "I/O_EXPANDER_3") (pin "INT") (pinfunction "INT_INT") (pintype "bidirectional"))
    )
    (net (code "79") (name "unconnected-(I/O_EXPANDER_4-PadINT)") (class "Default")
      (node (ref "I/O_EXPANDER_4") (pin "INT") (pinfunction "INT_INT") (pintype "bidirectional"))
    )
    (net (code "80") (name "unconnected-(I/O_EXPANDER_5-PadINT)") (class "Default")
      (node (ref "I/O_EXPANDER_5") (pin "INT") (pinfunction "INT_INT") (pintype "bidirectional"))
    )
    (net (code "81") (name "unconnected-(I/O_EXPANDER_6-PadINT)") (class "Default")
      (node (ref "I/O_EXPANDER_6") (pin "INT") (pinfunction "INT_INT") (pintype "bidirectional"))
    )
    (net (code "82") (name "unconnected-(U$26-PadINT)") (class "Default")
      (node (ref "U$26") (pin "INT") (pinfunction "INT_INT") (pintype "bidirectional"))
    )
  )
)
